# Cp.net
KiCad netlist of a schematic drawn in Altium Designer
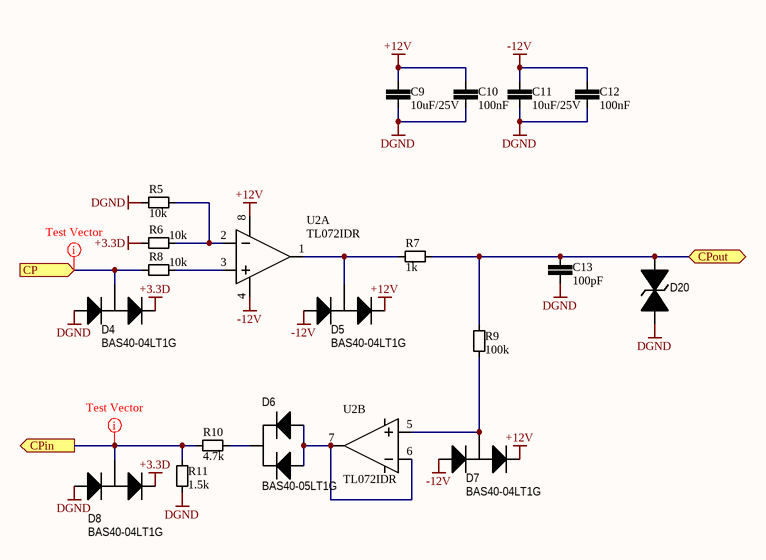
[diagram p0: Cp.SchDoc]

(export (version "E")
  (design (tool "Eeschema 10.0.6"))
  (components
    (comp (ref "C9")
      (value "10uF/25V")
      (footprint "GreenBox:1206-C")
      (description "MLCC 10uF 10% 25V X7R 1206")
      (fields (field (name "Comment") "Cap") (field (name "PUBLISHER") "GreenBox"))
      (libsource (lib "Capacitor") (part "C21E010UK1E0"))
    )
    (comp (ref "C10")
      (value "100nF")
      (footprint "GreenBox:0603-C")
      (description "MLCC 100nF 10% 50V X7R 0603")
      (fields (field (name "Comment") "Cap") (field (name "PUBLISHER") "GreenBox"))
      (libsource (lib "Capacitor") (part "C21C100NK1H0"))
    )
    (comp (ref "C11")
      (value "10uF/25V")
      (footprint "GreenBox:1206-C")
      (description "MLCC 10uF 10% 25V X7R 1206")
      (fields (field (name "Comment") "Cap") (field (name "PUBLISHER") "GreenBox"))
      (libsource (lib "Capacitor") (part "C21E010UK1E0"))
    )
    (comp (ref "C12")
      (value "100nF")
      (footprint "GreenBox:0603-C")
      (description "MLCC 100nF 10% 50V X7R 0603")
      (fields (field (name "Comment") "Cap") (field (name "PUBLISHER") "GreenBox"))
      (libsource (lib "Capacitor") (part "C21C100NK1H0"))
    )
    (comp (ref "C13")
      (value "100pF")
      (footprint "GreenBox:0603-C")
      (description "MLCC 100pF 5% 50V NPO 0603")
      (fields (field (name "Comment") "Cap") (field (name "PUBLISHER") "GreenBox"))
      (libsource (lib "Capacitor") (part "C11C100PJ1H0"))
    )
    (comp (ref "D4")
      (value "BAS40-04LT1G")
      (footprint "GreenBox:SOT-23_N")
      (description "Dual Series Schottky Barrier Diode BAS40-04LT1G Vrrm 40V If 0.12A Ir 1uA")
      (fields (field (name "MANUFACTURER") "ON SEMICONDUCTOR") (field (name "PUBLISHER") "GreenBox"))
      (libsource (lib "Diode_Transistor") (part "D742BAS4004O"))
    )
    (comp (ref "D5")
      (value "BAS40-04LT1G")
      (footprint "GreenBox:SOT-23_N")
      (description "Dual Series Schottky Barrier Diode BAS40-04LT1G Vrrm 40V If 0.12A Ir 1uA")
      (fields (field (name "MANUFACTURER") "ON SEMICONDUCTOR") (field (name "PUBLISHER") "GreenBox"))
      (libsource (lib "Diode_Transistor") (part "D742BAS4004O"))
    )
    (comp (ref "D6")
      (value "BAS40-05LT1G")
      (footprint "GreenBox:SOT-23_N")
      (description "Dual Series Schottky Barrier Diode BAS40-05LT1G Vrrm 40V If 0.12A Ir 1uA")
      (fields (field (name "MANUFACTURER") "ON SEMICONDUCTOR") (field (name "PUBLISHER") "GreenBox"))
      (libsource (lib "Diode_Transistor") (part "D842BAS4005O"))
    )
    (comp (ref "D7")
      (value "BAS40-04LT1G")
      (footprint "GreenBox:SOT-23_N")
      (description "Dual Series Schottky Barrier Diode BAS40-04LT1G Vrrm 40V If 0.12A Ir 1uA")
      (fields (field (name "MANUFACTURER") "ON SEMICONDUCTOR") (field (name "PUBLISHER") "GreenBox"))
      (libsource (lib "Diode_Transistor") (part "D742BAS4004O"))
    )
    (comp (ref "D8")
      (value "BAS40-04LT1G")
      (footprint "GreenBox:SOT-23_N")
      (description "Dual Series Schottky Barrier Diode BAS40-04LT1G Vrrm 40V If 0.12A Ir 1uA")
      (fields (field (name "MANUFACTURER") "ON SEMICONDUCTOR") (field (name "PUBLISHER") "GreenBox"))
      (libsource (lib "Diode_Transistor") (part "D742BAS4004O"))
    )
    (comp (ref "D20")
      (value "SMAJ12CA")
      (footprint "GreenBox:DO-214AC")
      (description "TVS BIDIRECTIONAL SMAJ12CA Vbr 13.3V Vc/Ipp 19.9V/20.1A")
      (fields (field (name "PUBLISHER") "GreenBox"))
      (libsource (lib "Diode_Transistor") (part "DT61SMAJ1220"))
    )
    (comp (ref "R5")
      (value "10k")
      (footprint "GreenBox:0603-R")
      (description "SMD Resistor 10k 1% 1/10W 0603 100PPM")
      (fields (field (name "Comment") "Res") (field (name "PUBLISHER") "GreenBox"))
      (libsource (lib "Resistor") (part "R11C010KFBF0"))
    )
    (comp (ref "R6")
      (value "10k")
      (footprint "GreenBox:0603-R")
      (description "SMD Resistor 10k 1% 1/10W 0603 100PPM")
      (fields (field (name "Comment") "Res") (field (name "PUBLISHER") "GreenBox"))
      (libsource (lib "Resistor") (part "R11C010KFBF0"))
    )
    (comp (ref "R7")
      (value "1k")
      (footprint "GreenBox:0603-R")
      (description "SMD Resistor 1k 1% 1/10W 0603 100PPM")
      (fields (field (name "Comment") "Res") (field (name "PUBLISHER") "GreenBox"))
      (libsource (lib "Resistor") (part "R11C001KFBF0"))
    )
    (comp (ref "R8")
      (value "10k")
      (footprint "GreenBox:0603-R")
      (description "SMD Resistor 10k 1% 1/10W 0603 100PPM")
      (fields (field (name "Comment") "Res") (field (name "PUBLISHER") "GreenBox"))
      (libsource (lib "Resistor") (part "R11C010KFBF0"))
    )
    (comp (ref "R9")
      (value "100k")
      (footprint "GreenBox:0603-R")
      (description "SMD Resistor 100k 1% 1/10W 0603 100PPM")
      (fields (field (name "Comment") "Res") (field (name "PUBLISHER") "GreenBox"))
      (libsource (lib "Resistor") (part "R11C100KFBF0"))
    )
    (comp (ref "R10")
      (value "4.7k")
      (footprint "GreenBox:0603-R")
      (description "SMD Resistor 4.7k 1% 1/10W 0603 100PPM")
      (fields (field (name "Comment") "Res") (field (name "PUBLISHER") "GreenBox"))
      (libsource (lib "Resistor") (part "R11C04K7FBF0"))
    )
    (comp (ref "R11")
      (value "1.5k")
      (footprint "GreenBox:0603-R")
      (description "SMD Resistor 1.5k 1% 1/10W 0603 100PPM")
      (fields (field (name "Comment") "Res") (field (name "PUBLISHER") "GreenBox"))
      (libsource (lib "Resistor") (part "R11C01K5FBF0"))
    )
    (comp (ref "U2")
      (value "TL072IDR")
      (footprint "GreenBox:SO-8_N")
      (description "Dual Operational Amplifier TL072IDR Vcc ±18V Vio 3mV")
      (fields (field (name "MANUFACTURER") "TEXAS INSTRUMENTS") (field (name "PUBLISHER") "GreenBox"))
      (libsource (lib "OPAMP") (part "UOS1TLC072IT"))
    )
  )
  (nets
    (net (code "1") (name "+3.3D") (class "Default")
      (node (ref "D4") (pin "2") (pinfunction "K_2") (pintype "passive"))
      (node (ref "D8") (pin "2") (pinfunction "K_2") (pintype "passive"))
      (node (ref "R6") (pin "1") (pinfunction "1_1") (pintype "passive"))
    )
    (net (code "2") (name "+12V") (class "Default")
      (node (ref "C10") (pin "1") (pinfunction "1_1") (pintype "passive"))
      (node (ref "C9") (pin "1") (pinfunction "1_1") (pintype "passive"))
      (node (ref "D5") (pin "2") (pinfunction "K_2") (pintype "passive"))
      (node (ref "D7") (pin "2") (pinfunction "K_2") (pintype "passive"))
      (node (ref "U2") (pin "8") (pintype "passive"))
    )
    (net (code "3") (name "-12V") (class "Default")
      (node (ref "C11") (pin "1") (pinfunction "1_1") (pintype "passive"))
      (node (ref "C12") (pin "1") (pinfunction "1_1") (pintype "passive"))
      (node (ref "D5") (pin "1") (pinfunction "A_1") (pintype "passive"))
      (node (ref "D7") (pin "1") (pinfunction "A_1") (pintype "passive"))
      (node (ref "U2") (pin "4") (pintype "passive"))
    )
    (net (code "4") (name "/CP") (class "Default")
      (node (ref "D4") (pin "3") (pinfunction "C_3") (pintype "passive"))
      (node (ref "R8") (pin "1") (pinfunction "1_1") (pintype "passive"))
    )
    (net (code "5") (name "/CPin") (class "Default")
      (node (ref "D8") (pin "3") (pinfunction "C_3") (pintype "passive"))
      (node (ref "R10") (pin "1") (pinfunction "1_1") (pintype "passive"))
      (node (ref "R11") (pin "2") (pinfunction "2_2") (pintype "passive"))
    )
    (net (code "6") (name "/CPout") (class "Default")
      (node (ref "C13") (pin "1") (pinfunction "1_1") (pintype "passive"))
      (node (ref "D20") (pin "2") (pinfunction "2_2") (pintype "passive"))
      (node (ref "R7") (pin "2") (pinfunction "2_2") (pintype "passive"))
      (node (ref "R9") (pin "1") (pinfunction "1_1") (pintype "passive"))
    )
    (net (code "7") (name "DGND") (class "Default")
      (node (ref "C10") (pin "2") (pinfunction "2_2") (pintype "passive"))
      (node (ref "C11") (pin "2") (pinfunction "2_2") (pintype "passive"))
      (node (ref "C12") (pin "2") (pinfunction "2_2") (pintype "passive"))
      (node (ref "C13") (pin "2") (pinfunction "2_2") (pintype "passive"))
      (node (ref "C9") (pin "2") (pinfunction "2_2") (pintype "passive"))
      (node (ref "D20") (pin "1") (pinfunction "1_1") (pintype "passive"))
      (node (ref "D4") (pin "1") (pinfunction "A_1") (pintype "passive"))
      (node (ref "D8") (pin "1") (pinfunction "A_1") (pintype "passive"))
      (node (ref "R11") (pin "1") (pinfunction "1_1") (pintype "passive"))
      (node (ref "R5") (pin "1") (pinfunction "1_1") (pintype "passive"))
    )
    (net (code "8") (name "Net-(D5-C)") (class "Default")
      (node (ref "D5") (pin "3") (pinfunction "C_3") (pintype "passive"))
      (node (ref "R7") (pin "1") (pinfunction "1_1") (pintype "passive"))
      (node (ref "U2") (pin "1") (pintype "passive"))
    )
    (net (code "9") (name "Net-(D6-Pad1)") (class "Default")
      (node (ref "D6") (pin "1") (pinfunction "1_1") (pintype "passive"))
      (node (ref "D6") (pin "2") (pinfunction "2_2") (pintype "passive"))
      (node (ref "U2") (pin "6") (pintype "passive"))
      (node (ref "U2") (pin "7") (pintype "passive"))
    )
    (net (code "10") (name "Net-(D6-Pad3)") (class "Default")
      (node (ref "D6") (pin "3") (pinfunction "3_3") (pintype "passive"))
      (node (ref "R10") (pin "2") (pinfunction "2_2") (pintype "passive"))
    )
    (net (code "11") (name "Net-(D7-C)") (class "Default")
      (node (ref "D7") (pin "3") (pinfunction "C_3") (pintype "passive"))
      (node (ref "R9") (pin "2") (pinfunction "2_2") (pintype "passive"))
      (node (ref "U2") (pin "5") (pintype "passive"))
    )
    (net (code "12") (name "Net-(R5-Pad2)") (class "Default")
      (node (ref "R5") (pin "2") (pinfunction "2_2") (pintype "passive"))
      (node (ref "R6") (pin "2") (pinfunction "2_2") (pintype "passive"))
      (node (ref "U2") (pin "2") (pintype "passive"))
    )
    (net (code "13") (name "Net-(R8-Pad2)") (class "Default")
      (node (ref "R8") (pin "2") (pinfunction "2_2") (pintype "passive"))
      (node (ref "U2") (pin "3") (pintype "passive"))
    )
  )
)
